# usupply.net
KiCad netlist of a schematic drawn in EAGLE
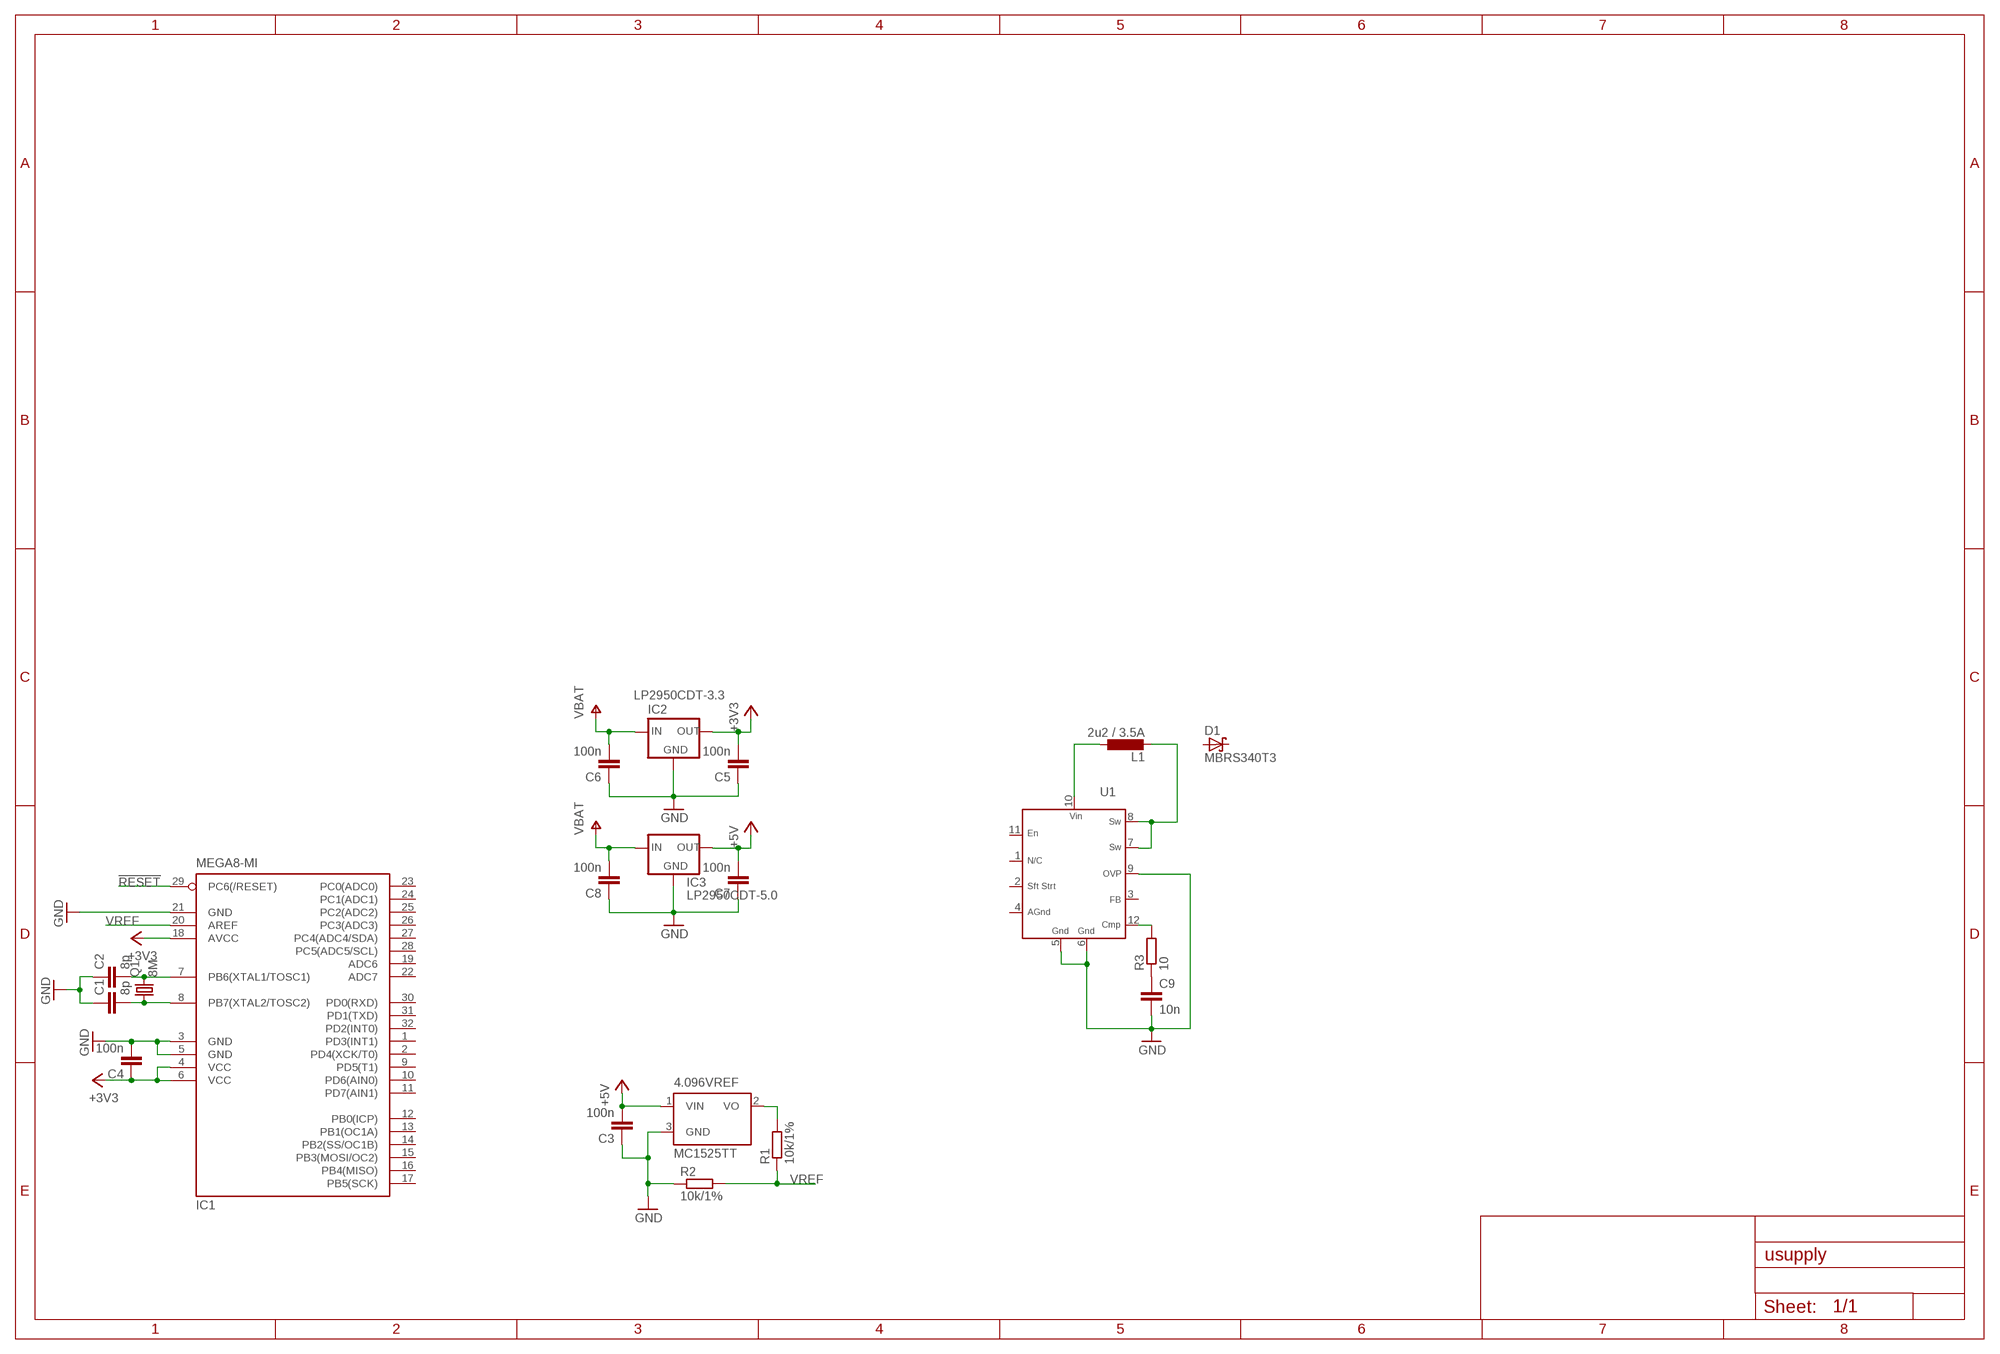
[diagram p0: schematic, sheet 1]

(export (version "E")
  (design (tool "Eeschema 10.0.6"))
  (components
    (comp (ref "4.096VREF")
      (value "MC1525TT")
      (footprint "eagle-import:SOT23")
      (libsource (lib "eagle-import") (part "MC15TT25"))
    )
    (comp (ref "C1")
      (value "8p")
      (footprint "eagle-import:C0805")
      (libsource (lib "eagle-import") (part "C-EUC0805"))
    )
    (comp (ref "C2")
      (value "8p")
      (footprint "eagle-import:C0805")
      (libsource (lib "eagle-import") (part "C-EUC0805"))
    )
    (comp (ref "C3")
      (value "100n")
      (footprint "eagle-import:C0805")
      (libsource (lib "eagle-import") (part "C-EUC0805"))
    )
    (comp (ref "C4")
      (value "100n")
      (footprint "eagle-import:C0805")
      (libsource (lib "eagle-import") (part "C-EUC0805"))
    )
    (comp (ref "C5")
      (value "100n")
      (footprint "eagle-import:C0805")
      (libsource (lib "eagle-import") (part "C-EUC0805"))
    )
    (comp (ref "C6")
      (value "100n")
      (footprint "eagle-import:C0805")
      (libsource (lib "eagle-import") (part "C-EUC0805"))
    )
    (comp (ref "C7")
      (value "100n")
      (footprint "eagle-import:C0805")
      (libsource (lib "eagle-import") (part "C-EUC0805"))
    )
    (comp (ref "C8")
      (value "100n")
      (footprint "eagle-import:C0805")
      (libsource (lib "eagle-import") (part "C-EUC0805"))
    )
    (comp (ref "C9")
      (value "10n")
      (footprint "eagle-import:C0805")
      (libsource (lib "eagle-import") (part "C-EUC0805"))
    )
    (comp (ref "D1")
      (value "MBRS340T3")
      (footprint "eagle-import:SMC")
      (libsource (lib "eagle-import") (part "MBRS30T34"))
    )
    (comp (ref "IC1")
      (value "MEGA8-MI")
      (footprint "eagle-import:MLF32")
      (fields (field (name "MPN") "ATMEGA88PA-MU"))
      (libsource (lib "eagle-import") (part "MEGA8-MI"))
    )
    (comp (ref "IC2")
      (value "LP2950CDT-3.3")
      (footprint "eagle-import:DPACK")
      (libsource (lib "eagle-import") (part "LP2950?CDT-3.3"))
    )
    (comp (ref "IC3")
      (value "LP2950CDT-5.0")
      (footprint "eagle-import:DPACK")
      (libsource (lib "eagle-import") (part "LP2950?CDT-5.0"))
    )
    (comp (ref "L1")
      (value "2u2 / 3.5A")
      (footprint "eagle-import:PIS2816")
      (libsource (lib "eagle-import") (part "L-EUPIS2816"))
    )
    (comp (ref "Q1")
      (value "8M")
      (footprint "eagle-import:HC49U-V")
      (libsource (lib "eagle-import") (part "CRYSTALHC49U-V"))
    )
    (comp (ref "R1")
      (value "10k/1%")
      (footprint "eagle-import:M0805")
      (libsource (lib "eagle-import") (part "R-EU_M0805"))
    )
    (comp (ref "R2")
      (value "10k/1%")
      (footprint "eagle-import:M0805")
      (libsource (lib "eagle-import") (part "R-EU_M0805"))
    )
    (comp (ref "R3")
      (value "10")
      (footprint "eagle-import:M0805")
      (libsource (lib "eagle-import") (part "R-EU_M0805"))
    )
    (comp (ref "U1")
      (value "MIC2253")
      (footprint "eagle-import:MLF12_3.0MM_X_3.0MM")
      (libsource (lib "eagle-import") (part "MIC2253"))
    )
  )
  (nets
    (net (code "1") (name "+3V3") (class "Default")
      (node (ref "C4") (pin "1") (pinfunction "1_1") (pintype "passive"))
      (node (ref "C5") (pin "2") (pinfunction "2_2") (pintype "passive"))
      (node (ref "IC1") (pin "18") (pinfunction "AVCC_18") (pintype "power_in"))
      (node (ref "IC1") (pin "4") (pinfunction "VCC_4") (pintype "power_in"))
      (node (ref "IC1") (pin "6") (pinfunction "VCC_6") (pintype "power_in"))
      (node (ref "IC2") (pin "3") (pinfunction "OUT_3") (pintype "passive"))
    )
    (net (code "2") (name "+5V") (class "Default")
      (node (ref "4.096VREF") (pin "1") (pinfunction "VIN_1") (pintype "input"))
      (node (ref "C3") (pin "2") (pinfunction "2_2") (pintype "passive"))
      (node (ref "C7") (pin "2") (pinfunction "2_2") (pintype "passive"))
      (node (ref "IC3") (pin "3") (pinfunction "OUT_3") (pintype "passive"))
    )
    (net (code "3") (name "/VREF") (class "Default")
      (node (ref "IC1") (pin "20") (pinfunction "AREF_20") (pintype "passive"))
      (node (ref "R1") (pin "1") (pinfunction "1_1") (pintype "passive"))
      (node (ref "R2") (pin "2") (pinfunction "2_2") (pintype "passive"))
    )
    (net (code "4") (name "/~{RESET}") (class "Default")
      (node (ref "IC1") (pin "29") (pinfunction "PC6(/RESET)_29") (pintype "bidirectional"))
    )
    (net (code "5") (name "GND") (class "Default")
      (node (ref "4.096VREF") (pin "3") (pinfunction "GND_3") (pintype "passive"))
      (node (ref "C1") (pin "1") (pinfunction "1_1") (pintype "passive"))
      (node (ref "C2") (pin "1") (pinfunction "1_1") (pintype "passive"))
      (node (ref "C3") (pin "1") (pinfunction "1_1") (pintype "passive"))
      (node (ref "C4") (pin "2") (pinfunction "2_2") (pintype "passive"))
      (node (ref "C5") (pin "1") (pinfunction "1_1") (pintype "passive"))
      (node (ref "C6") (pin "1") (pinfunction "1_1") (pintype "passive"))
      (node (ref "C7") (pin "1") (pinfunction "1_1") (pintype "passive"))
      (node (ref "C8") (pin "1") (pinfunction "1_1") (pintype "passive"))
      (node (ref "C9") (pin "2") (pinfunction "2_2") (pintype "passive"))
      (node (ref "IC1") (pin "21") (pinfunction "GND_21") (pintype "power_in"))
      (node (ref "IC1") (pin "3") (pinfunction "GND_3") (pintype "power_in"))
      (node (ref "IC1") (pin "5") (pinfunction "GND_5") (pintype "power_in"))
      (node (ref "IC2") (pin "4") (pinfunction "GND_4") (pintype "input"))
      (node (ref "IC3") (pin "4") (pinfunction "GND_4") (pintype "input"))
      (node (ref "R2") (pin "1") (pinfunction "1_1") (pintype "passive"))
      (node (ref "U1") (pin "5") (pinfunction "GND_5") (pintype "passive"))
      (node (ref "U1") (pin "6") (pinfunction "GND_6") (pintype "passive"))
      (node (ref "U1") (pin "9") (pinfunction "OVP_9") (pintype "passive"))
    )
    (net (code "6") (name "Net-(4.096VREF-VO)") (class "Default")
      (node (ref "4.096VREF") (pin "2") (pinfunction "VO_2") (pintype "output"))
      (node (ref "R1") (pin "2") (pinfunction "2_2") (pintype "passive"))
    )
    (net (code "7") (name "Net-(C9-Pad1)") (class "Default")
      (node (ref "C9") (pin "1") (pinfunction "1_1") (pintype "passive"))
      (node (ref "R3") (pin "1") (pinfunction "1_1") (pintype "passive"))
    )
    (net (code "8") (name "Net-(IC1-PB6(XTAL1{slash}TOSC1))") (class "Default")
      (node (ref "C2") (pin "2") (pinfunction "2_2") (pintype "passive"))
      (node (ref "IC1") (pin "7") (pinfunction "PB6(XTAL1/TOSC1)_7") (pintype "bidirectional"))
      (node (ref "Q1") (pin "2") (pinfunction "2_2") (pintype "passive"))
    )
    (net (code "9") (name "Net-(IC1-PB7(XTAL2{slash}TOSC2))") (class "Default")
      (node (ref "C1") (pin "2") (pinfunction "2_2") (pintype "passive"))
      (node (ref "IC1") (pin "8") (pinfunction "PB7(XTAL2/TOSC2)_8") (pintype "bidirectional"))
      (node (ref "Q1") (pin "1") (pinfunction "1_1") (pintype "passive"))
    )
    (net (code "10") (name "Net-(L1-Pad2)") (class "Default")
      (node (ref "L1") (pin "2") (pinfunction "2_2") (pintype "passive"))
      (node (ref "U1") (pin "7") (pinfunction "SW_7") (pintype "open_collector"))
      (node (ref "U1") (pin "8") (pinfunction "SW_8") (pintype "open_collector"))
    )
    (net (code "11") (name "Net-(U1-CMP)") (class "Default")
      (node (ref "R3") (pin "2") (pinfunction "2_2") (pintype "passive"))
      (node (ref "U1") (pin "12") (pinfunction "CMP_12") (pintype "passive"))
    )
    (net (code "12") (name "Net-(U1-VIN)") (class "Default")
      (node (ref "L1") (pin "1") (pinfunction "1_1") (pintype "passive"))
      (node (ref "U1") (pin "10") (pinfunction "VIN_10") (pintype "passive"))
    )
    (net (code "13") (name "VBAT") (class "Default")
      (node (ref "C6") (pin "2") (pinfunction "2_2") (pintype "passive"))
      (node (ref "C8") (pin "2") (pinfunction "2_2") (pintype "passive"))
      (node (ref "IC2") (pin "1") (pinfunction "IN_1") (pintype "input"))
      (node (ref "IC3") (pin "1") (pinfunction "IN_1") (pintype "input"))
    )
    (net (code "14") (name "unconnected-(D1-PadA)") (class "Default")
      (node (ref "D1") (pin "A") (pinfunction "A_A") (pintype "passive"))
    )
    (net (code "15") (name "unconnected-(D1-PadC)") (class "Default")
      (node (ref "D1") (pin "C") (pinfunction "C_C") (pintype "passive"))
    )
    (net (code "16") (name "unconnected-(IC1-ADC6-Pad19)") (class "Default")
      (node (ref "IC1") (pin "19") (pinfunction "ADC6_19") (pintype "bidirectional"))
    )
    (net (code "17") (name "unconnected-(IC1-ADC7-Pad22)") (class "Default")
      (node (ref "IC1") (pin "22") (pinfunction "ADC7_22") (pintype "bidirectional"))
    )
    (net (code "18") (name "unconnected-(IC1-PB0(ICP)-Pad12)") (class "Default")
      (node (ref "IC1") (pin "12") (pinfunction "PB0(ICP)_12") (pintype "bidirectional"))
    )
    (net (code "19") (name "unconnected-(IC1-PB1(OC1A)-Pad13)") (class "Default")
      (node (ref "IC1") (pin "13") (pinfunction "PB1(OC1A)_13") (pintype "bidirectional"))
    )
    (net (code "20") (name "unconnected-(IC1-PB2(SS{slash}OC1B)-Pad14)") (class "Default")
      (node (ref "IC1") (pin "14") (pinfunction "PB2(SS/OC1B)_14") (pintype "bidirectional"))
    )
    (net (code "21") (name "unconnected-(IC1-PB3(MOSI{slash}OC2)-Pad15)") (class "Default")
      (node (ref "IC1") (pin "15") (pinfunction "PB3(MOSI/OC2)_15") (pintype "bidirectional"))
    )
    (net (code "22") (name "unconnected-(IC1-PB4(MISO)-Pad16)") (class "Default")
      (node (ref "IC1") (pin "16") (pinfunction "PB4(MISO)_16") (pintype "bidirectional"))
    )
    (net (code "23") (name "unconnected-(IC1-PB5(SCK)-Pad17)") (class "Default")
      (node (ref "IC1") (pin "17") (pinfunction "PB5(SCK)_17") (pintype "bidirectional"))
    )
    (net (code "24") (name "unconnected-(IC1-PC0(ADC0)-Pad23)") (class "Default")
      (node (ref "IC1") (pin "23") (pinfunction "PC0(ADC0)_23") (pintype "bidirectional"))
    )
    (net (code "25") (name "unconnected-(IC1-PC1(ADC1)-Pad24)") (class "Default")
      (node (ref "IC1") (pin "24") (pinfunction "PC1(ADC1)_24") (pintype "bidirectional"))
    )
    (net (code "26") (name "unconnected-(IC1-PC2(ADC2)-Pad25)") (class "Default")
      (node (ref "IC1") (pin "25") (pinfunction "PC2(ADC2)_25") (pintype "bidirectional"))
    )
    (net (code "27") (name "unconnected-(IC1-PC3(ADC3)-Pad26)") (class "Default")
      (node (ref "IC1") (pin "26") (pinfunction "PC3(ADC3)_26") (pintype "bidirectional"))
    )
    (net (code "28") (name "unconnected-(IC1-PC4(ADC4{slash}SDA)-Pad27)") (class "Default")
      (node (ref "IC1") (pin "27") (pinfunction "PC4(ADC4/SDA)_27") (pintype "bidirectional"))
    )
    (net (code "29") (name "unconnected-(IC1-PC5(ADC5{slash}SCL)-Pad28)") (class "Default")
      (node (ref "IC1") (pin "28") (pinfunction "PC5(ADC5/SCL)_28") (pintype "bidirectional"))
    )
    (net (code "30") (name "unconnected-(IC1-PD0(RXD)-Pad30)") (class "Default")
      (node (ref "IC1") (pin "30") (pinfunction "PD0(RXD)_30") (pintype "bidirectional"))
    )
    (net (code "31") (name "unconnected-(IC1-PD1(TXD)-Pad31)") (class "Default")
      (node (ref "IC1") (pin "31") (pinfunction "PD1(TXD)_31") (pintype "bidirectional"))
    )
    (net (code "32") (name "unconnected-(IC1-PD2(INT0)-Pad32)") (class "Default")
      (node (ref "IC1") (pin "32") (pinfunction "PD2(INT0)_32") (pintype "bidirectional"))
    )
    (net (code "33") (name "unconnected-(IC1-PD3(INT1)-Pad1)") (class "Default")
      (node (ref "IC1") (pin "1") (pinfunction "PD3(INT1)_1") (pintype "bidirectional"))
    )
    (net (code "34") (name "unconnected-(IC1-PD4(XCK{slash}T0)-Pad2)") (class "Default")
      (node (ref "IC1") (pin "2") (pinfunction "PD4(XCK/T0)_2") (pintype "bidirectional"))
    )
    (net (code "35") (name "unconnected-(IC1-PD5(T1)-Pad9)") (class "Default")
      (node (ref "IC1") (pin "9") (pinfunction "PD5(T1)_9") (pintype "bidirectional"))
    )
    (net (code "36") (name "unconnected-(IC1-PD6(AIN0)-Pad10)") (class "Default")
      (node (ref "IC1") (pin "10") (pinfunction "PD6(AIN0)_10") (pintype "bidirectional"))
    )
    (net (code "37") (name "unconnected-(IC1-PD7(AIN1)-Pad11)") (class "Default")
      (node (ref "IC1") (pin "11") (pinfunction "PD7(AIN1)_11") (pintype "bidirectional"))
    )
    (net (code "38") (name "unconnected-(U1-AGND-Pad4)") (class "Default")
      (node (ref "U1") (pin "4") (pinfunction "AGND_4") (pintype "passive"))
    )
    (net (code "39") (name "unconnected-(U1-EN-Pad11)") (class "Default")
      (node (ref "U1") (pin "11") (pinfunction "EN_11") (pintype "input"))
    )
    (net (code "40") (name "unconnected-(U1-FB-Pad3)") (class "Default")
      (node (ref "U1") (pin "3") (pinfunction "FB_3") (pintype "passive"))
    )
    (net (code "41") (name "unconnected-(U1-NC-Pad1)") (class "Default")
      (node (ref "U1") (pin "1") (pinfunction "NC_1") (pintype "no_connect"))
    )
    (net (code "42") (name "unconnected-(U1-SS-Pad2)") (class "Default")
      (node (ref "U1") (pin "2") (pinfunction "SS_2") (pintype "passive"))
    )
  )
)
